# p2hex-001.net
KiCad netlist of a schematic drawn in EAGLE
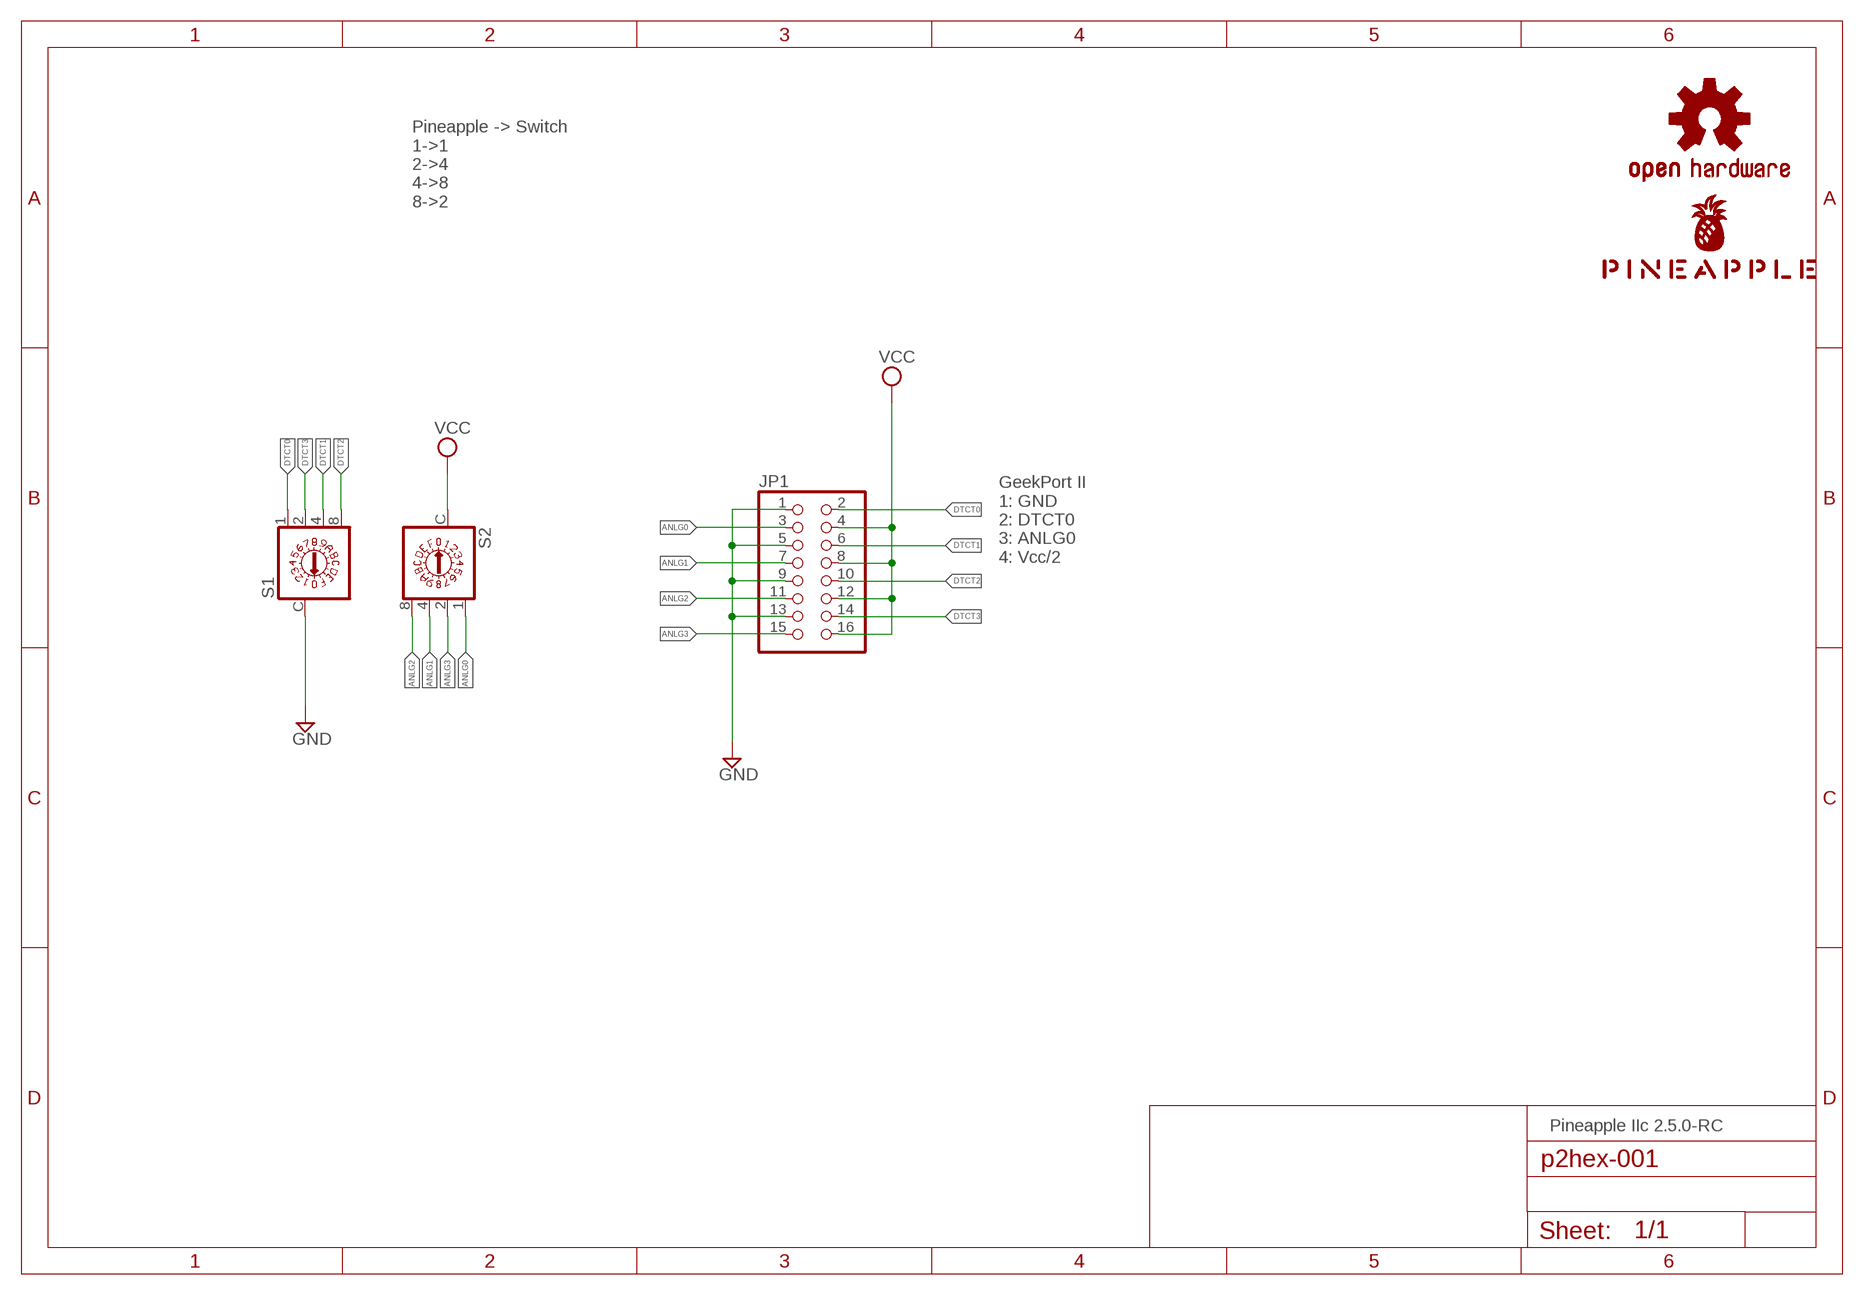
[diagram p0: schematic, sheet 1]

(export (version "E")
  (design (tool "Eeschema 10.0.6"))
  (components
    (comp (ref "JP1")
      (value "PINHD-2X8")
      (footprint "eagle-import:2X08")
      (libsource (lib "eagle-import") (part "PINHD-2X8"))
    )
    (comp (ref "LOGO1")
      (value "OSHW-LOGOS-COPPER")
      (footprint "eagle-import:OSHW-LOGO-S_COPPER")
      (libsource (lib "eagle-import") (part "OSHW-LOGOS-COPPER"))
    )
    (comp (ref "S1")
      (value "A1353HEX")
      (footprint "eagle-import:A1353HEX")
      (libsource (lib "eagle-import") (part "A1353HEX"))
    )
    (comp (ref "S2")
      (value "A1353HEX")
      (footprint "eagle-import:A1353HEX")
      (libsource (lib "eagle-import") (part "A1353HEX"))
    )
    (comp (ref "U$1")
      (value "PINEAPPLE450_SILK")
      (footprint "eagle-import:PINEAPPLE450_SILK")
      (libsource (lib "eagle-import") (part "PINEAPPLE450_SILK"))
    )
  )
  (nets
    (net (code "1") (name "ANLG0") (class "Default")
      (node (ref "JP1") (pin "3") (pinfunction "3_3") (pintype "passive"))
      (node (ref "S2") (pin "1") (pinfunction "1_1") (pintype "passive"))
    )
    (net (code "2") (name "ANLG1") (class "Default")
      (node (ref "JP1") (pin "7") (pinfunction "7_7") (pintype "passive"))
      (node (ref "S2") (pin "4") (pinfunction "4_4") (pintype "passive"))
    )
    (net (code "3") (name "ANLG2") (class "Default")
      (node (ref "JP1") (pin "11") (pinfunction "11_11") (pintype "passive"))
      (node (ref "S2") (pin "8") (pinfunction "8_8") (pintype "passive"))
    )
    (net (code "4") (name "ANLG3") (class "Default")
      (node (ref "JP1") (pin "15") (pinfunction "15_15") (pintype "passive"))
      (node (ref "S2") (pin "2") (pinfunction "2_2") (pintype "passive"))
    )
    (net (code "5") (name "DTCT0") (class "Default")
      (node (ref "JP1") (pin "2") (pinfunction "2_2") (pintype "passive"))
      (node (ref "S1") (pin "1") (pinfunction "1_1") (pintype "passive"))
    )
    (net (code "6") (name "DTCT1") (class "Default")
      (node (ref "JP1") (pin "6") (pinfunction "6_6") (pintype "passive"))
      (node (ref "S1") (pin "4") (pinfunction "4_4") (pintype "passive"))
    )
    (net (code "7") (name "DTCT2") (class "Default")
      (node (ref "JP1") (pin "10") (pinfunction "10_10") (pintype "passive"))
      (node (ref "S1") (pin "8") (pinfunction "8_8") (pintype "passive"))
    )
    (net (code "8") (name "DTCT3") (class "Default")
      (node (ref "JP1") (pin "14") (pinfunction "14_14") (pintype "passive"))
      (node (ref "S1") (pin "2") (pinfunction "2_2") (pintype "passive"))
    )
    (net (code "9") (name "GND") (class "Default")
      (node (ref "JP1") (pin "1") (pinfunction "1_1") (pintype "passive"))
      (node (ref "JP1") (pin "13") (pinfunction "13_13") (pintype "passive"))
      (node (ref "JP1") (pin "5") (pinfunction "5_5") (pintype "passive"))
      (node (ref "JP1") (pin "9") (pinfunction "9_9") (pintype "passive"))
      (node (ref "S1") (pin "C") (pinfunction "C_C") (pintype "passive"))
    )
    (net (code "10") (name "VCC") (class "Default")
      (node (ref "JP1") (pin "12") (pinfunction "12_12") (pintype "passive"))
      (node (ref "JP1") (pin "16") (pinfunction "16_16") (pintype "passive"))
      (node (ref "JP1") (pin "4") (pinfunction "4_4") (pintype "passive"))
      (node (ref "JP1") (pin "8") (pinfunction "8_8") (pintype "passive"))
      (node (ref "S2") (pin "C") (pinfunction "C_C") (pintype "passive"))
    )
  )
)
